# ScoreBoard-V2.net
KiCad netlist of a schematic drawn in EAGLE
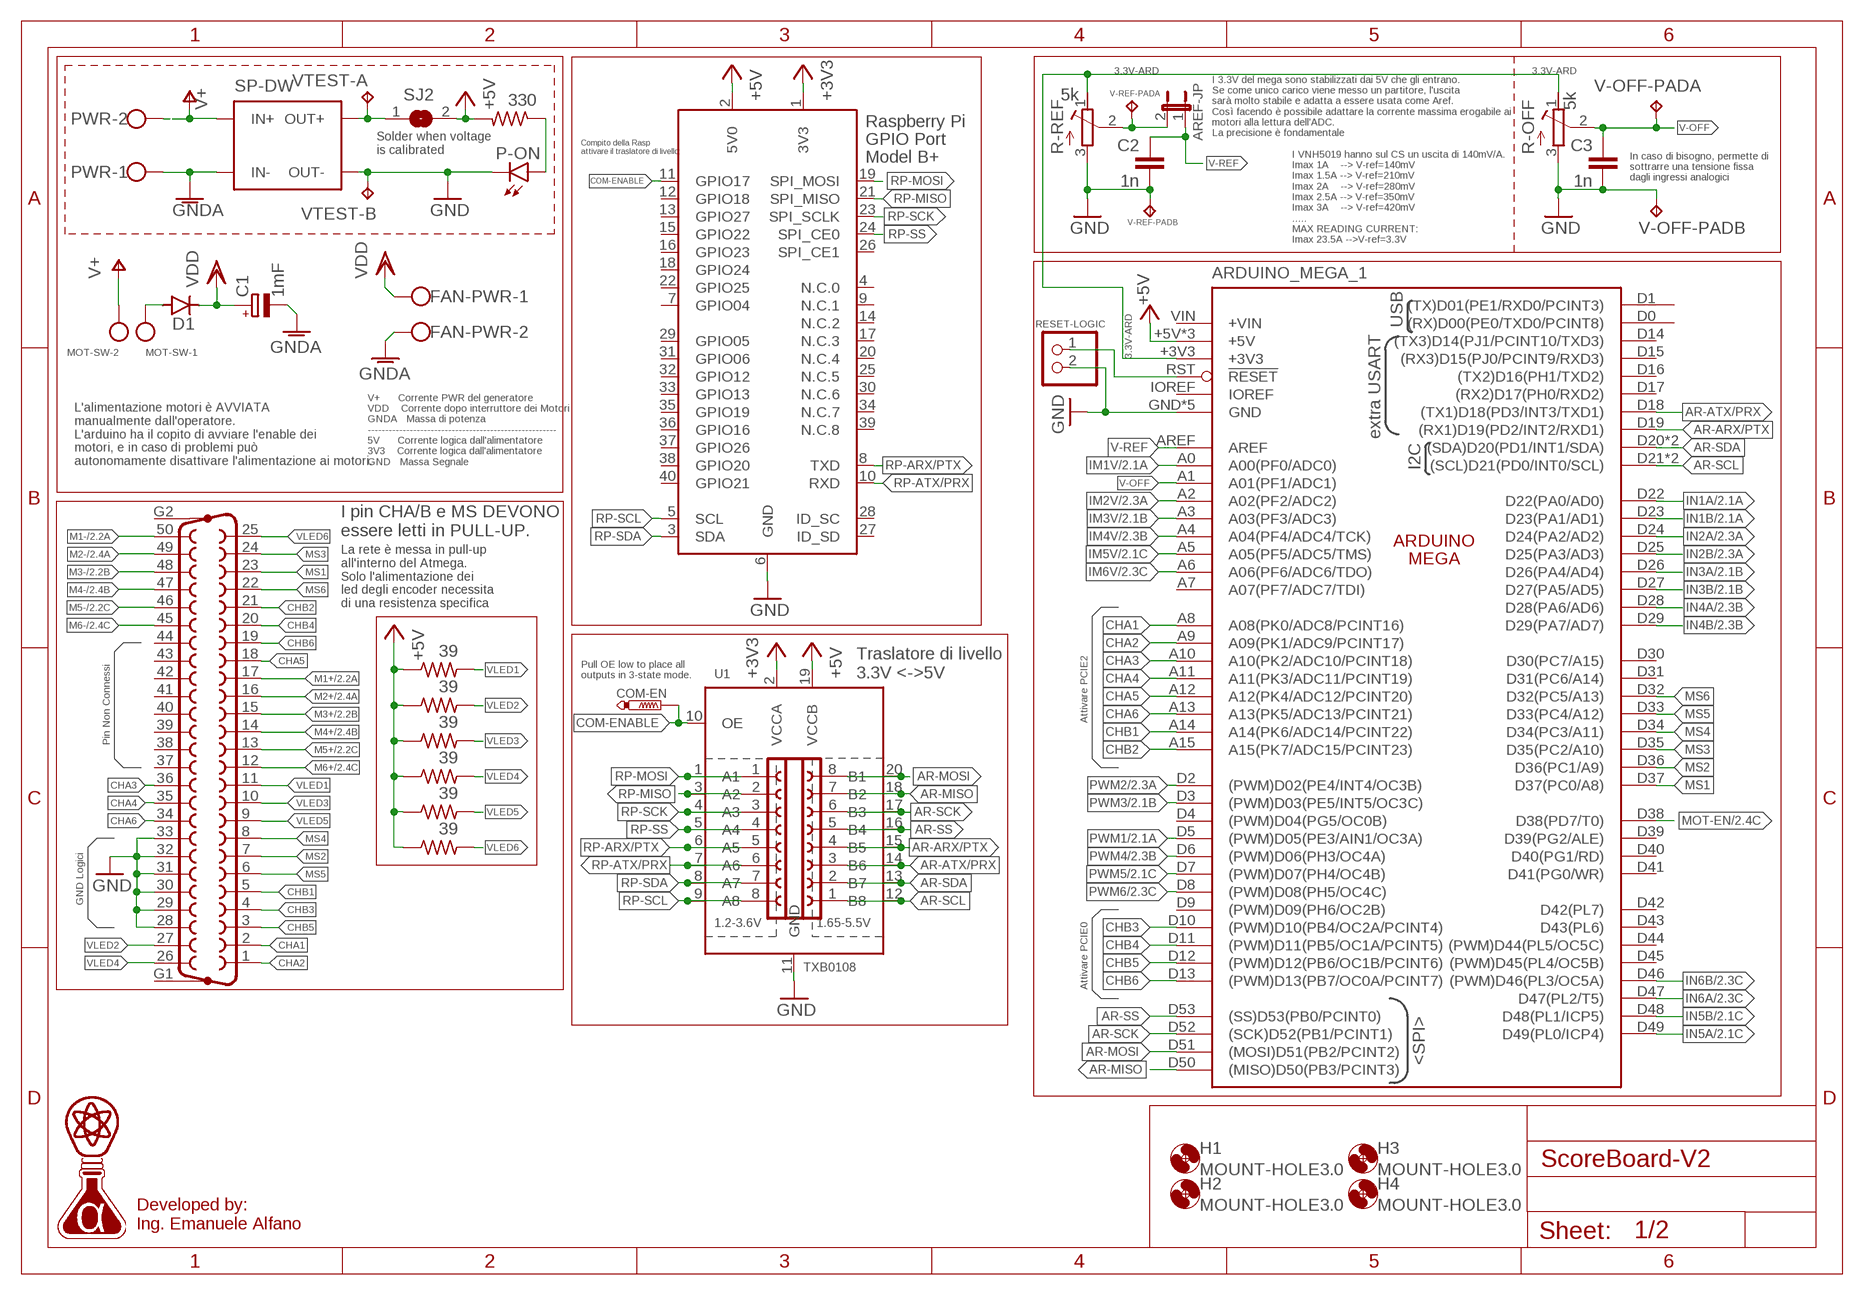
[diagram p0: schematic, sheet 1]
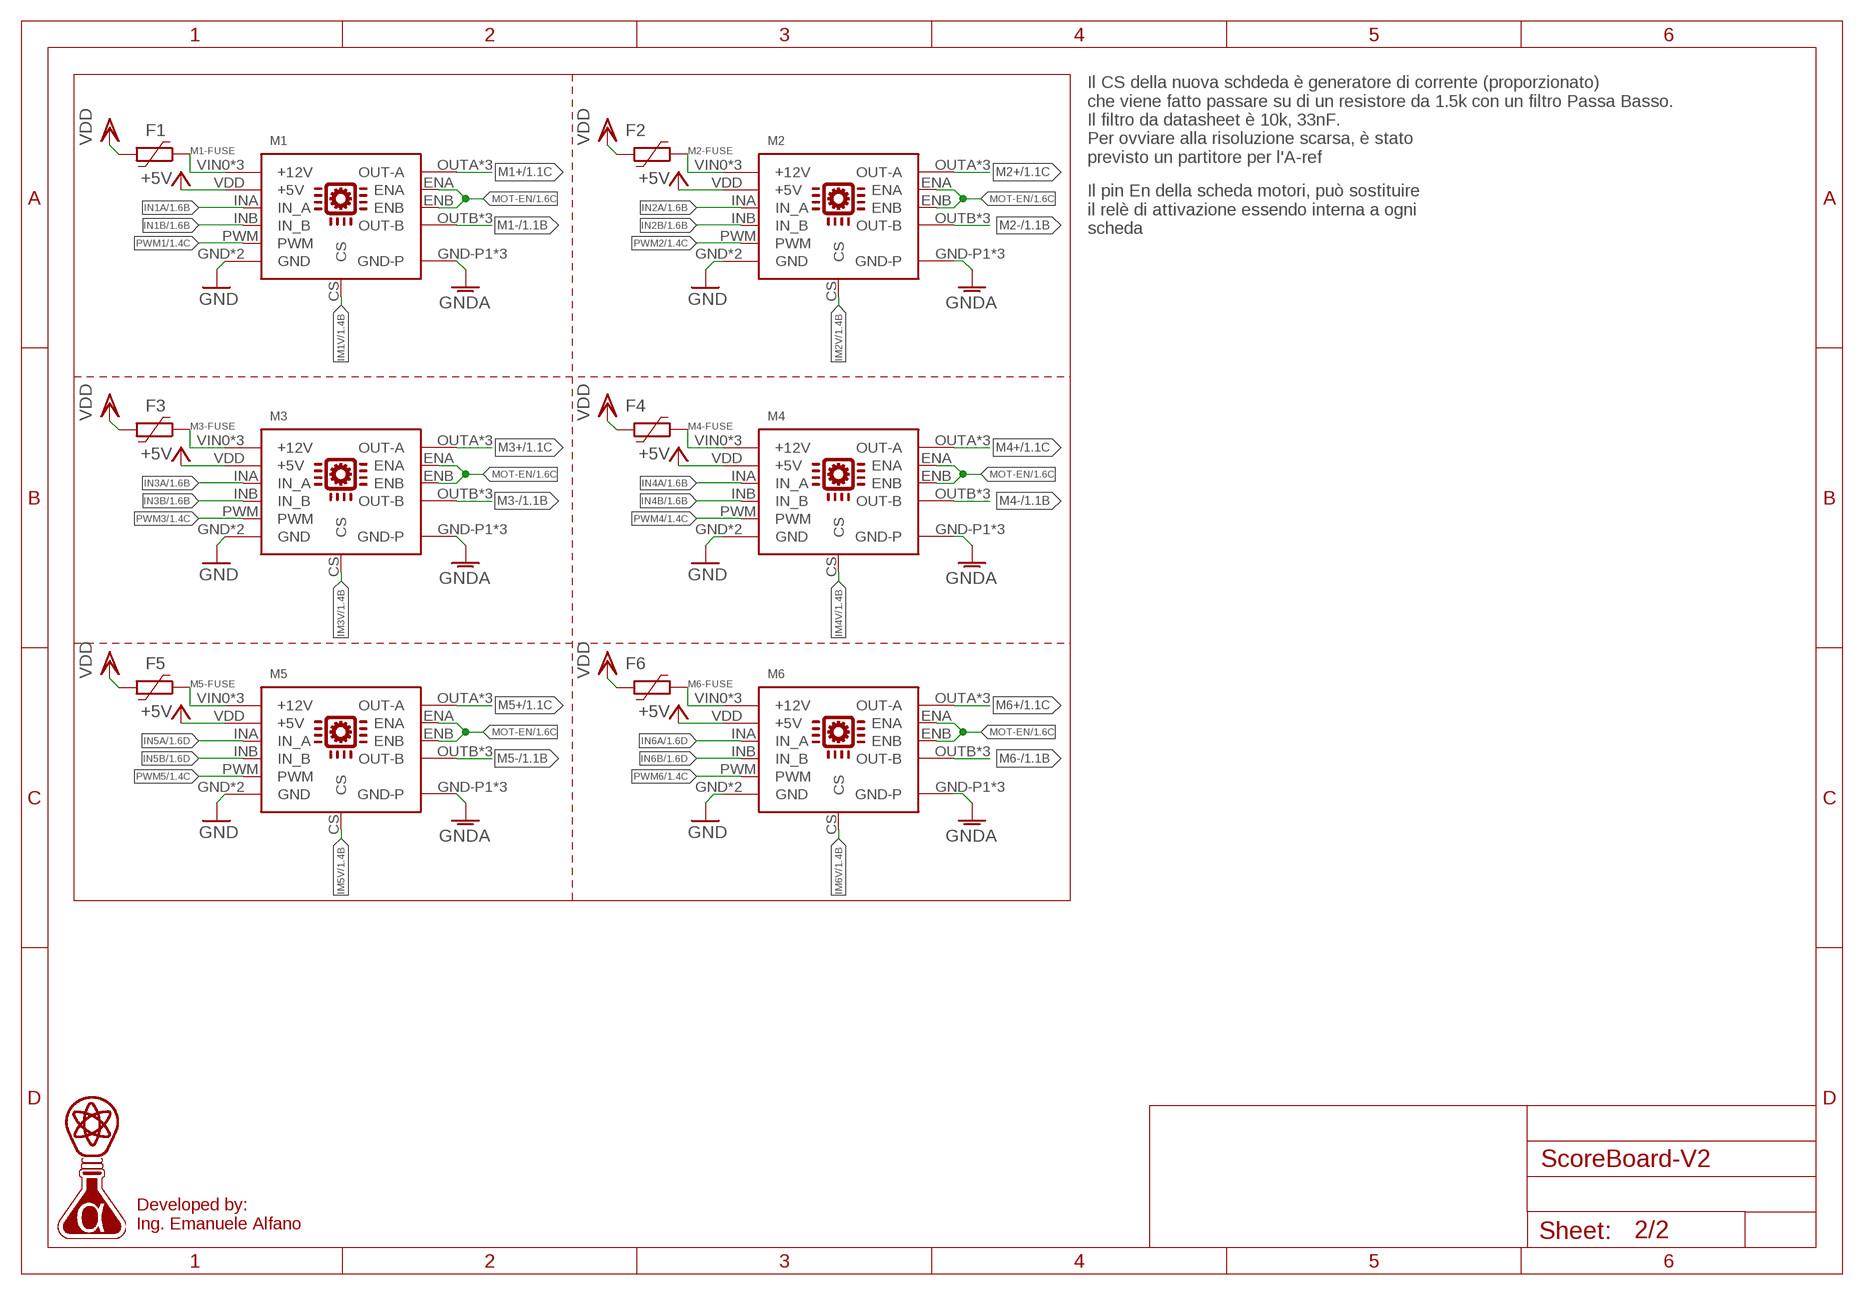
[diagram p1: schematic, sheet 2]

(export (version "E")
  (design (tool "Eeschema 10.0.6"))
  (components
    (comp (ref "F1")
      (value "2410-BOX")
      (footprint "eagle-import:BELFUSE0679-3000-12")
      (libsource (lib "eagle-import") (part "?2410-BOX"))
    )
    (comp (ref "F2")
      (value "2410-BOX")
      (footprint "eagle-import:BELFUSE0679-3000-12")
      (libsource (lib "eagle-import") (part "?2410-BOX"))
    )
    (comp (ref "F3")
      (value "2410-BOX")
      (footprint "eagle-import:BELFUSE0679-3000-12")
      (libsource (lib "eagle-import") (part "?2410-BOX"))
    )
    (comp (ref "F4")
      (value "2410-BOX")
      (footprint "eagle-import:BELFUSE0679-3000-12")
      (libsource (lib "eagle-import") (part "?2410-BOX"))
    )
    (comp (ref "F5")
      (value "2410-BOX")
      (footprint "eagle-import:BELFUSE0679-3000-12")
      (libsource (lib "eagle-import") (part "?2410-BOX"))
    )
    (comp (ref "F6")
      (value "2410-BOX")
      (footprint "eagle-import:BELFUSE0679-3000-12")
      (libsource (lib "eagle-import") (part "?2410-BOX"))
    )
    (comp (ref "M1")
      (value "VNH5019")
      (footprint "eagle-import:VNH5019")
      (libsource (lib "eagle-import") (part "VNH5019"))
    )
    (comp (ref "M2")
      (value "VNH5019")
      (footprint "eagle-import:VNH5019")
      (libsource (lib "eagle-import") (part "VNH5019"))
    )
    (comp (ref "M3")
      (value "VNH5019")
      (footprint "eagle-import:VNH5019")
      (libsource (lib "eagle-import") (part "VNH5019"))
    )
    (comp (ref "M4")
      (value "VNH5019")
      (footprint "eagle-import:VNH5019")
      (libsource (lib "eagle-import") (part "VNH5019"))
    )
    (comp (ref "M5")
      (value "VNH5019")
      (footprint "eagle-import:VNH5019")
      (libsource (lib "eagle-import") (part "VNH5019"))
    )
    (comp (ref "M6")
      (value "VNH5019")
      (footprint "eagle-import:VNH5019")
      (libsource (lib "eagle-import") (part "VNH5019"))
    )
    (comp (ref "ARDUINO_MEGA_1")
      (value "MEGA_ARDUINONO-HOLE")
      (footprint "eagle-import:MEGA-NO-HOLE")
      (libsource (lib "eagle-import") (part "MEGA_ARDUINONO-HOLE"))
    )
    (comp (ref "AREF-JP")
      (value "JP1E")
      (footprint "eagle-import:JP1")
      (libsource (lib "eagle-import") (part "JP1E"))
    )
    (comp (ref "C1")
      (value "1mF")
      (footprint "eagle-import:E5-13")
      (libsource (lib "eagle-import") (part "CPOL-EUE5-13"))
    )
    (comp (ref "C2")
      (value "1n")
      (footprint "eagle-import:C025-024X044")
      (libsource (lib "eagle-import") (part "C-EU025-024X044"))
    )
    (comp (ref "C3")
      (value "1n")
      (footprint "eagle-import:C025-024X044")
      (libsource (lib "eagle-import") (part "C-EU025-024X044"))
    )
    (comp (ref "COM-EN")
      (value "PTR1PAD1-13")
      (footprint "eagle-import:P1-13")
      (libsource (lib "eagle-import") (part "PTR1PAD1-13"))
    )
    (comp (ref "D-SUB50")
      (value "F50VP")
      (footprint "eagle-import:F50VP")
      (libsource (lib "eagle-import") (part "F50VP"))
    )
    (comp (ref "D1")
      (value "ES2D")
      (footprint "eagle-import:SMB")
      (libsource (lib "eagle-import") (part "ES2D"))
    )
    (comp (ref "FAN-PWR")
      (value "W237-102")
      (footprint "eagle-import:W237-102")
      (fields (field (name "MPN") "237-102"))
      (libsource (lib "eagle-import") (part "W237-102"))
    )
    (comp (ref "H1")
      (value "MOUNT-HOLE3.0")
      (footprint "eagle-import:3,0")
      (libsource (lib "eagle-import") (part "MOUNT-HOLE3.0"))
    )
    (comp (ref "H2")
      (value "MOUNT-HOLE3.0")
      (footprint "eagle-import:3,0")
      (libsource (lib "eagle-import") (part "MOUNT-HOLE3.0"))
    )
    (comp (ref "H3")
      (value "MOUNT-HOLE3.0")
      (footprint "eagle-import:3,0")
      (libsource (lib "eagle-import") (part "MOUNT-HOLE3.0"))
    )
    (comp (ref "H4")
      (value "MOUNT-HOLE3.0")
      (footprint "eagle-import:3,0")
      (libsource (lib "eagle-import") (part "MOUNT-HOLE3.0"))
    )
    (comp (ref "MOT-SW")
      (value "W237-102")
      (footprint "eagle-import:W237-102")
      (fields (field (name "MPN") "237-102"))
      (libsource (lib "eagle-import") (part "W237-102"))
    )
    (comp (ref "P-ON")
      (value "LED3MM")
      (footprint "eagle-import:LED3MM")
      (libsource (lib "eagle-import") (part "LED3MM"))
    )
    (comp (ref "PWR")
      (value "W237-102")
      (footprint "eagle-import:W237-102")
      (fields (field (name "MPN") "237-102"))
      (libsource (lib "eagle-import") (part "W237-102"))
    )
    (comp (ref "R-OFF")
      (value "5k")
      (footprint "eagle-import:RTRIMT93YA")
      (libsource (lib "eagle-import") (part "R-TRIMMT93YA"))
    )
    (comp (ref "R-REF")
      (value "5k")
      (footprint "eagle-import:RTRIMT93YA")
      (libsource (lib "eagle-import") (part "R-TRIMMT93YA"))
    )
    (comp (ref "R1")
      (value "39")
      (footprint "eagle-import:0204_5")
      (libsource (lib "eagle-import") (part "R-US_0204/5"))
    )
    (comp (ref "R2")
      (value "39")
      (footprint "eagle-import:0204_5")
      (libsource (lib "eagle-import") (part "R-US_0204/5"))
    )
    (comp (ref "R3")
      (value "39")
      (footprint "eagle-import:0204_5")
      (libsource (lib "eagle-import") (part "R-US_0204/5"))
    )
    (comp (ref "R4")
      (value "39")
      (footprint "eagle-import:0204_5")
      (libsource (lib "eagle-import") (part "R-US_0204/5"))
    )
    (comp (ref "R5")
      (value "39")
      (footprint "eagle-import:0204_5")
      (libsource (lib "eagle-import") (part "R-US_0204/5"))
    )
    (comp (ref "R6")
      (value "39")
      (footprint "eagle-import:0204_5")
      (libsource (lib "eagle-import") (part "R-US_0204/5"))
    )
    (comp (ref "RASPBERRY-PY")
      (value "RASPI_GPIO_B+_BOX")
      (footprint "eagle-import:RASPI_GPIO_B+_BOX")
      (libsource (lib "eagle-import") (part "RASPI_GPIO_B+_BOX"))
    )
    (comp (ref "RESET-LOGIC")
      (value "PINHD-1X2")
      (footprint "eagle-import:1X02")
      (libsource (lib "eagle-import") (part "PINHD-1X2"))
    )
    (comp (ref "RL")
      (value "330")
      (footprint "eagle-import:0204_7")
      (libsource (lib "eagle-import") (part "R-US_0204/7"))
    )
    (comp (ref "SJ2")
      (value "SJ")
      (footprint "eagle-import:SJ")
      (fields (field (name "SPICEPREFIX") "B"))
      (libsource (lib "eagle-import") (part "SJ"))
    )
    (comp (ref "SP-DW")
      (value "DC/DC-STEP-DOWNGLOB")
      (footprint "eagle-import:DC_DC-STEP-DOWN-UNIVERSAL")
      (libsource (lib "eagle-import") (part "DC/DC-STEP-DOWNGLOB"))
    )
    (comp (ref "SV1")
      (value "FE08-1")
      (footprint "eagle-import:FE08")
      (libsource (lib "eagle-import") (part "FE08-1"))
    )
    (comp (ref "SV2")
      (value "FE08-1")
      (footprint "eagle-import:FE08")
      (libsource (lib "eagle-import") (part "FE08-1"))
    )
    (comp (ref "U1")
      (value "TXB0108")
      (footprint "eagle-import:TSSOP20")
      (fields (field (name "MF") "Texas Instruments") (field (name "MP") "TXB0108PWR"))
      (libsource (lib "eagle-import") (part "TXB0108PWR"))
    )
    (comp (ref "V-OFF-PAD")
      (value "TP2P2-38-17")
      (footprint "eagle-import:P2-38-17")
      (fields (field (name "SPICEPREFIX") "X"))
      (libsource (lib "eagle-import") (part "TP2P2-38-17"))
    )
    (comp (ref "V-REF-PAD")
      (value "TP2P2-38-17")
      (footprint "eagle-import:P2-38-17")
      (fields (field (name "SPICEPREFIX") "X"))
      (libsource (lib "eagle-import") (part "TP2P2-38-17"))
    )
    (comp (ref "VTEST-")
      (value "TP2P2-38-17")
      (footprint "eagle-import:P2-38-17")
      (fields (field (name "SPICEPREFIX") "X"))
      (libsource (lib "eagle-import") (part "TP2P2-38-17"))
    )
  )
  (nets
    (net (code "1") (name "+3V3") (class "Default")
      (node (ref "RASPBERRY-PY") (pin "1") (pinfunction "3V3_1") (pintype "power_in"))
      (node (ref "U1") (pin "2") (pinfunction "VCCA_2") (pintype "bidirectional"))
    )
    (net (code "2") (name "+5V") (class "Default")
      (node (ref "ARDUINO_MEGA_1") (pin "+5V") (pinfunction "+5V_+5V") (pintype "bidirectional"))
      (node (ref "ARDUINO_MEGA_1") (pin "+5V1") (pinfunction "+5V_+5V1") (pintype "bidirectional"))
      (node (ref "ARDUINO_MEGA_1") (pin "+5V2") (pinfunction "+5V_+5V2") (pintype "bidirectional"))
      (node (ref "M1") (pin "VDD") (pinfunction "+5V_VDD") (pintype "bidirectional"))
      (node (ref "M2") (pin "VDD") (pinfunction "+5V_VDD") (pintype "bidirectional"))
      (node (ref "M3") (pin "VDD") (pinfunction "+5V_VDD") (pintype "bidirectional"))
      (node (ref "M4") (pin "VDD") (pinfunction "+5V_VDD") (pintype "bidirectional"))
      (node (ref "M5") (pin "VDD") (pinfunction "+5V_VDD") (pintype "bidirectional"))
      (node (ref "M6") (pin "VDD") (pinfunction "+5V_VDD") (pintype "bidirectional"))
      (node (ref "R1") (pin "1") (pinfunction "1_1") (pintype "passive"))
      (node (ref "R2") (pin "1") (pinfunction "1_1") (pintype "passive"))
      (node (ref "R3") (pin "1") (pinfunction "1_1") (pintype "passive"))
      (node (ref "R4") (pin "1") (pinfunction "1_1") (pintype "passive"))
      (node (ref "R5") (pin "1") (pinfunction "1_1") (pintype "passive"))
      (node (ref "R6") (pin "1") (pinfunction "1_1") (pintype "passive"))
      (node (ref "RASPBERRY-PY") (pin "2") (pinfunction "5V0_2") (pintype "power_in"))
      (node (ref "RL") (pin "2") (pinfunction "2_2") (pintype "passive"))
      (node (ref "SJ2") (pin "2") (pinfunction "2_2") (pintype "passive"))
      (node (ref "U1") (pin "19") (pinfunction "VCCB_19") (pintype "bidirectional"))
    )
    (net (code "3") (name "3.3V-ARD") (class "Default")
      (node (ref "ARDUINO_MEGA_1") (pin "+3V3") (pinfunction "+3V3_+3V3") (pintype "bidirectional"))
      (node (ref "R-OFF") (pin "1") (pinfunction "E_1") (pintype "passive"))
      (node (ref "R-REF") (pin "1") (pinfunction "E_1") (pintype "passive"))
    )
    (net (code "4") (name "AR-ARX{slash}PTX") (class "Default")
      (node (ref "ARDUINO_MEGA_1") (pin "D19") (pinfunction "(RX1)D19(PD2/INT2/RXD1)_D19") (pintype "bidirectional"))
      (node (ref "SV2") (pin "4") (pinfunction "4_4") (pintype "passive"))
      (node (ref "U1") (pin "15") (pinfunction "B5_15") (pintype "bidirectional"))
    )
    (net (code "5") (name "AR-ATX{slash}PRX") (class "Default")
      (node (ref "ARDUINO_MEGA_1") (pin "D18") (pinfunction "(TX1)D18(PD3/INT3/TXD1)_D18") (pintype "bidirectional"))
      (node (ref "SV2") (pin "3") (pinfunction "3_3") (pintype "passive"))
      (node (ref "U1") (pin "14") (pinfunction "B6_14") (pintype "bidirectional"))
    )
    (net (code "6") (name "AR-MISO") (class "Default")
      (node (ref "ARDUINO_MEGA_1") (pin "D50") (pinfunction "(MISO)D50(PB3/PCINT3)_D50") (pintype "bidirectional"))
      (node (ref "SV2") (pin "7") (pinfunction "7_7") (pintype "passive"))
      (node (ref "U1") (pin "18") (pinfunction "B2_18") (pintype "bidirectional"))
    )
    (net (code "7") (name "AR-MOSI") (class "Default")
      (node (ref "ARDUINO_MEGA_1") (pin "D51") (pinfunction "(MOSI)D51(PB2/PCINT2)_D51") (pintype "bidirectional"))
      (node (ref "SV2") (pin "8") (pinfunction "8_8") (pintype "passive"))
      (node (ref "U1") (pin "20") (pinfunction "B1_20") (pintype "bidirectional"))
    )
    (net (code "8") (name "AR-SCK") (class "Default")
      (node (ref "ARDUINO_MEGA_1") (pin "D52") (pinfunction "(SCK)D52(PB1/PCINT1)_D52") (pintype "bidirectional"))
      (node (ref "SV2") (pin "6") (pinfunction "6_6") (pintype "passive"))
      (node (ref "U1") (pin "17") (pinfunction "B3_17") (pintype "bidirectional"))
    )
    (net (code "9") (name "AR-SCL") (class "Default")
      (node (ref "ARDUINO_MEGA_1") (pin "D21") (pinfunction "(SCL)D21(PD0/INT0/SCL)_D21") (pintype "bidirectional"))
      (node (ref "ARDUINO_MEGA_1") (pin "SCL1") (pinfunction "(SCL)D21(PD0/INT0/SCL)_SCL1") (pintype "bidirectional"))
      (node (ref "SV2") (pin "1") (pinfunction "1_1") (pintype "passive"))
      (node (ref "U1") (pin "12") (pinfunction "B8_12") (pintype "bidirectional"))
    )
    (net (code "10") (name "AR-SDA") (class "Default")
      (node (ref "ARDUINO_MEGA_1") (pin "D20") (pinfunction "(SDA)D20(PD1/INT1/SDA)_D20") (pintype "bidirectional"))
      (node (ref "ARDUINO_MEGA_1") (pin "SDA1") (pinfunction "(SDA)D20(PD1/INT1/SDA)_SDA1") (pintype "bidirectional"))
      (node (ref "SV2") (pin "2") (pinfunction "2_2") (pintype "passive"))
      (node (ref "U1") (pin "13") (pinfunction "B7_13") (pintype "bidirectional"))
    )
    (net (code "11") (name "AR-SS") (class "Default")
      (node (ref "ARDUINO_MEGA_1") (pin "D53") (pinfunction "(SS)D53(PB0/PCINT0)_D53") (pintype "bidirectional"))
      (node (ref "SV2") (pin "5") (pinfunction "5_5") (pintype "passive"))
      (node (ref "U1") (pin "16") (pinfunction "B4_16") (pintype "bidirectional"))
    )
    (net (code "12") (name "CHA1") (class "Default")
      (node (ref "ARDUINO_MEGA_1") (pin "A8") (pinfunction "A08(PK0/ADC8/PCINT16)_A8") (pintype "bidirectional"))
      (node (ref "D-SUB50") (pin "2") (pinfunction "2_2") (pintype "passive"))
    )
    (net (code "13") (name "CHA2") (class "Default")
      (node (ref "ARDUINO_MEGA_1") (pin "A9") (pinfunction "A09(PK1/ADC9/PCINT17)_A9") (pintype "bidirectional"))
      (node (ref "D-SUB50") (pin "1") (pinfunction "1_1") (pintype "passive"))
    )
    (net (code "14") (name "CHA3") (class "Default")
      (node (ref "ARDUINO_MEGA_1") (pin "A10") (pinfunction "A10(PK2/ADC10/PCINT18)_A10") (pintype "bidirectional"))
      (node (ref "D-SUB50") (pin "36") (pinfunction "36_36") (pintype "passive"))
    )
    (net (code "15") (name "CHA4") (class "Default")
      (node (ref "ARDUINO_MEGA_1") (pin "A11") (pinfunction "A11(PK3/ADC11/PCINT19)_A11") (pintype "bidirectional"))
      (node (ref "D-SUB50") (pin "35") (pinfunction "35_35") (pintype "passive"))
    )
    (net (code "16") (name "CHA5") (class "Default")
      (node (ref "ARDUINO_MEGA_1") (pin "A12") (pinfunction "A12(PK4/ADC12/PCINT20)_A12") (pintype "bidirectional"))
      (node (ref "D-SUB50") (pin "18") (pinfunction "18_18") (pintype "passive"))
    )
    (net (code "17") (name "CHA6") (class "Default")
      (node (ref "ARDUINO_MEGA_1") (pin "A13") (pinfunction "A13(PK5/ADC13/PCINT21)_A13") (pintype "bidirectional"))
      (node (ref "D-SUB50") (pin "34") (pinfunction "34_34") (pintype "passive"))
    )
    (net (code "18") (name "CHB1") (class "Default")
      (node (ref "ARDUINO_MEGA_1") (pin "A14") (pinfunction "A14(PK6/ADC14/PCINT22)_A14") (pintype "bidirectional"))
      (node (ref "D-SUB50") (pin "5") (pinfunction "5_5") (pintype "passive"))
    )
    (net (code "19") (name "CHB2") (class "Default")
      (node (ref "ARDUINO_MEGA_1") (pin "A15") (pinfunction "A15(PK7/ADC15/PCINT23)_A15") (pintype "bidirectional"))
      (node (ref "D-SUB50") (pin "21") (pinfunction "21_21") (pintype "passive"))
    )
    (net (code "20") (name "CHB3") (class "Default")
      (node (ref "ARDUINO_MEGA_1") (pin "D10") (pinfunction "(PWM)D10(PB4/OC2A/PCINT4)_D10") (pintype "bidirectional"))
      (node (ref "D-SUB50") (pin "4") (pinfunction "4_4") (pintype "passive"))
    )
    (net (code "21") (name "CHB4") (class "Default")
      (node (ref "ARDUINO_MEGA_1") (pin "D11") (pinfunction "(PWM)D11(PB5/OC1A/PCINT5)_D11") (pintype "bidirectional"))
      (node (ref "D-SUB50") (pin "20") (pinfunction "20_20") (pintype "passive"))
    )
    (net (code "22") (name "CHB5") (class "Default")
      (node (ref "ARDUINO_MEGA_1") (pin "D12") (pinfunction "(PWM)D12(PB6/OC1B/PCINT6)_D12") (pintype "bidirectional"))
      (node (ref "D-SUB50") (pin "3") (pinfunction "3_3") (pintype "passive"))
    )
    (net (code "23") (name "CHB6") (class "Default")
      (node (ref "ARDUINO_MEGA_1") (pin "D13") (pinfunction "(PWM)D13(PB7/OC0A/PCINT7)_D13") (pintype "bidirectional"))
      (node (ref "D-SUB50") (pin "19") (pinfunction "19_19") (pintype "passive"))
    )
    (net (code "24") (name "COM-ENABLE") (class "Default")
      (node (ref "COM-EN") (pin "TP") (pinfunction "TP_TP") (pintype "input"))
      (node (ref "RASPBERRY-PY") (pin "11") (pinfunction "GPIO17_11") (pintype "bidirectional"))
      (node (ref "U1") (pin "10") (pinfunction "OE_10") (pintype "bidirectional"))
    )
    (net (code "25") (name "GND") (class "Default")
      (node (ref "ARDUINO_MEGA_1") (pin "GND") (pinfunction "GND_GND") (pintype "bidirectional"))
      (node (ref "ARDUINO_MEGA_1") (pin "GND1") (pinfunction "GND_GND1") (pintype "bidirectional"))
      (node (ref "ARDUINO_MEGA_1") (pin "GND2") (pinfunction "GND_GND2") (pintype "bidirectional"))
      (node (ref "ARDUINO_MEGA_1") (pin "GND3") (pinfunction "GND_GND3") (pintype "bidirectional"))
      (node (ref "ARDUINO_MEGA_1") (pin "GND4") (pinfunction "GND_GND4") (pintype "bidirectional"))
      (node (ref "C2") (pin "2") (pinfunction "2_2") (pintype "passive"))
      (node (ref "C3") (pin "2") (pinfunction "2_2") (pintype "passive"))
      (node (ref "D-SUB50") (pin "28") (pinfunction "28_28") (pintype "passive"))
      (node (ref "D-SUB50") (pin "29") (pinfunction "29_29") (pintype "passive"))
      (node (ref "D-SUB50") (pin "30") (pinfunction "30_30") (pintype "passive"))
      (node (ref "D-SUB50") (pin "31") (pinfunction "31_31") (pintype "passive"))
      (node (ref "D-SUB50") (pin "32") (pinfunction "32_32") (pintype "passive"))
      (node (ref "D-SUB50") (pin "33") (pinfunction "33_33") (pintype "passive"))
      (node (ref "M1") (pin "GND") (pinfunction "GND_GND") (pintype "bidirectional"))
      (node (ref "M1") (pin "GND1") (pinfunction "GND_GND1") (pintype "bidirectional"))
      (node (ref "M2") (pin "GND") (pinfunction "GND_GND") (pintype "bidirectional"))
      (node (ref "M2") (pin "GND1") (pinfunction "GND_GND1") (pintype "bidirectional"))
      (node (ref "M3") (pin "GND") (pinfunction "GND_GND") (pintype "bidirectional"))
      (node (ref "M3") (pin "GND1") (pinfunction "GND_GND1") (pintype "bidirectional"))
      (node (ref "M4") (pin "GND") (pinfunction "GND_GND") (pintype "bidirectional"))
      (node (ref "M4") (pin "GND1") (pinfunction "GND_GND1") (pintype "bidirectional"))
      (node (ref "M5") (pin "GND") (pinfunction "GND_GND") (pintype "bidirectional"))
      (node (ref "M5") (pin "GND1") (pinfunction "GND_GND1") (pintype "bidirectional"))
      (node (ref "M6") (pin "GND") (pinfunction "GND_GND") (pintype "bidirectional"))
      (node (ref "M6") (pin "GND1") (pinfunction "GND_GND1") (pintype "bidirectional"))
      (node (ref "P-ON") (pin "K") (pinfunction "C_K") (pintype "passive"))
      (node (ref "R-OFF") (pin "3") (pinfunction "A_3") (pintype "passive"))
      (node (ref "R-REF") (pin "3") (pinfunction "A_3") (pintype "passive"))
      (node (ref "RASPBERRY-PY") (pin "6") (pinfunction "GND_6") (pintype "power_in"))
      (node (ref "RESET-LOGIC") (pin "2") (pinfunction "2_2") (pintype "passive"))
      (node (ref "SP-DW") (pin "OUT-") (pinfunction "OUT-_OUT-") (pintype "bidirectional"))
      (node (ref "SP-DW") (pin "OUT-1") (pinfunction "OUT-_OUT-1") (pintype "bidirectional"))
      (node (ref "SP-DW") (pin "OUT-2") (pinfunction "OUT-_OUT-2") (pintype "bidirectional"))
      (node (ref "U1") (pin "11") (pinfunction "GND_11") (pintype "bidirectional"))
      (node (ref "V-OFF-PAD") (pin "TP-2") (pinfunction "TP_TP-2") (pintype "input"))
      (node (ref "V-REF-PAD") (pin "TP-2") (pinfunction "TP_TP-2") (pintype "input"))
      (node (ref "VTEST-") (pin "TP-2") (pinfunction "TP_TP-2") (pintype "input"))
    )
    (net (code "26") (name "GNDA") (class "Default")
      (node (ref "C1") (pin "-") (pinfunction "-_-") (pintype "passive"))
      (node (ref "FAN-PWR") (pin "2") (pinfunction "KL_2") (pintype "passive"))
      (node (ref "M1") (pin "GND-P1") (pinfunction "GND-P_GND-P1") (pintype "bidirectional"))
      (node (ref "M1") (pin "GND-P2") (pinfunction "GND-P_GND-P2") (pintype "bidirectional"))
      (node (ref "M1") (pin "GND-P3") (pinfunction "GND-P_GND-P3") (pintype "bidirectional"))
      (node (ref "M2") (pin "GND-P1") (pinfunction "GND-P_GND-P1") (pintype "bidirectional"))
      (node (ref "M2") (pin "GND-P2") (pinfunction "GND-P_GND-P2") (pintype "bidirectional"))
      (node (ref "M2") (pin "GND-P3") (pinfunction "GND-P_GND-P3") (pintype "bidirectional"))
      (node (ref "M3") (pin "GND-P1") (pinfunction "GND-P_GND-P1") (pintype "bidirectional"))
      (node (ref "M3") (pin "GND-P2") (pinfunction "GND-P_GND-P2") (pintype "bidirectional"))
      (node (ref "M3") (pin "GND-P3") (pinfunction "GND-P_GND-P3") (pintype "bidirectional"))
      (node (ref "M4") (pin "GND-P1") (pinfunction "GND-P_GND-P1") (pintype "bidirectional"))
      (node (ref "M4") (pin "GND-P2") (pinfunction "GND-P_GND-P2") (pintype "bidirectional"))
      (node (ref "M4") (pin "GND-P3") (pinfunction "GND-P_GND-P3") (pintype "bidirectional"))
      (node (ref "M5") (pin "GND-P1") (pinfunction "GND-P_GND-P1") (pintype "bidirectional"))
      (node (ref "M5") (pin "GND-P2") (pinfunction "GND-P_GND-P2") (pintype "bidirectional"))
      (node (ref "M5") (pin "GND-P3") (pinfunction "GND-P_GND-P3") (pintype "bidirectional"))
      (node (ref "M6") (pin "GND-P1") (pinfunction "GND-P_GND-P1") (pintype "bidirectional"))
      (node (ref "M6") (pin "GND-P2") (pinfunction "GND-P_GND-P2") (pintype "bidirectional"))
      (node (ref "M6") (pin "GND-P3") (pinfunction "GND-P_GND-P3") (pintype "bidirectional"))
      (node (ref "PWR") (pin "1") (pinfunction "KL_1") (pintype "passive"))
      (node (ref "SP-DW") (pin "IN-") (pinfunction "IN-_IN-") (pintype "bidirectional"))
      (node (ref "SP-DW") (pin "IN-1") (pinfunction "IN-_IN-1") (pintype "bidirectional"))
      (node (ref "SP-DW") (pin "IN-2") (pinfunction "IN-_IN-2") (pintype "bidirectional"))
    )
    (net (code "27") (name "IM1V") (class "Default")
      (node (ref "ARDUINO_MEGA_1") (pin "A0") (pinfunction "A00(PF0/ADC0)_A0") (pintype "bidirectional"))
      (node (ref "M1") (pin "CS") (pinfunction "CS_CS") (pintype "bidirectional"))
    )
    (net (code "28") (name "IM2V") (class "Default")
      (node (ref "ARDUINO_MEGA_1") (pin "A2") (pinfunction "A02(PF2/ADC2)_A2") (pintype "bidirectional"))
      (node (ref "M2") (pin "CS") (pinfunction "CS_CS") (pintype "bidirectional"))
    )
    (net (code "29") (name "IM3V") (class "Default")
      (node (ref "ARDUINO_MEGA_1") (pin "A3") (pinfunction "A03(PF3/ADC3)_A3") (pintype "bidirectional"))
      (node (ref "M3") (pin "CS") (pinfunction "CS_CS") (pintype "bidirectional"))
    )
    (net (code "30") (name "IM4V") (class "Default")
      (node (ref "ARDUINO_MEGA_1") (pin "A4") (pinfunction "A04(PF4/ADC4/TCK)_A4") (pintype "bidirectional"))
      (node (ref "M4") (pin "CS") (pinfunction "CS_CS") (pintype "bidirectional"))
    )
    (net (code "31") (name "IM5V") (class "Default")
      (node (ref "ARDUINO_MEGA_1") (pin "A5") (pinfunction "A05(PF5/ADC5/TMS)_A5") (pintype "bidirectional"))
      (node (ref "M5") (pin "CS") (pinfunction "CS_CS") (pintype "bidirectional"))
    )
    (net (code "32") (name "IM6V") (class "Default")
      (node (ref "ARDUINO_MEGA_1") (pin "A6") (pinfunction "A06(PF6/ADC6/TDO)_A6") (pintype "bidirectional"))
      (node (ref "M6") (pin "CS") (pinfunction "CS_CS") (pintype "bidirectional"))
    )
    (net (code "33") (name "IN1A") (class "Default")
      (node (ref "ARDUINO_MEGA_1") (pin "D22") (pinfunction "D22(PA0/AD0)_D22") (pintype "bidirectional"))
      (node (ref "M1") (pin "INA") (pinfunction "IN_A_INA") (pintype "bidirectional"))
    )
    (net (code "34") (name "IN1B") (class "Default")
      (node (ref "ARDUINO_MEGA_1") (pin "D23") (pinfunction "D23(PA1/AD1)_D23") (pintype "bidirectional"))
      (node (ref "M1") (pin "INB") (pinfunction "IN_B_INB") (pintype "bidirectional"))
    )
    (net (code "35") (name "IN2A") (class "Default")
      (node (ref "ARDUINO_MEGA_1") (pin "D24") (pinfunction "D24(PA2/AD2)_D24") (pintype "bidirectional"))
      (node (ref "M2") (pin "INA") (pinfunction "IN_A_INA") (pintype "bidirectional"))
    )
    (net (code "36") (name "IN2B") (class "Default")
      (node (ref "ARDUINO_MEGA_1") (pin "D25") (pinfunction "D25(PA3/AD3)_D25") (pintype "bidirectional"))
      (node (ref "M2") (pin "INB") (pinfunction "IN_B_INB") (pintype "bidirectional"))
    )
    (net (code "37") (name "IN3A") (class "Default")
      (node (ref "ARDUINO_MEGA_1") (pin "D26") (pinfunction "D26(PA4/AD4)_D26") (pintype "bidirectional"))
      (node (ref "M3") (pin "INA") (pinfunction "IN_A_INA") (pintype "bidirectional"))
    )
    (net (code "38") (name "IN3B") (class "Default")
      (node (ref "ARDUINO_MEGA_1") (pin "D27") (pinfunction "D27(PA5/AD5)_D27") (pintype "bidirectional"))
      (node (ref "M3") (pin "INB") (pinfunction "IN_B_INB") (pintype "bidirectional"))
    )
    (net (code "39") (name "IN4A") (class "Default")
      (node (ref "ARDUINO_MEGA_1") (pin "D28") (pinfunction "D28(PA6/AD6)_D28") (pintype "bidirectional"))
      (node (ref "M4") (pin "INA") (pinfunction "IN_A_INA") (pintype "bidirectional"))
    )
    (net (code "40") (name "IN4B") (class "Default")
      (node (ref "ARDUINO_MEGA_1") (pin "D29") (pinfunction "D29(PA7/AD7)_D29") (pintype "bidirectional"))
      (node (ref "M4") (pin "INB") (pinfunction "IN_B_INB") (pintype "bidirectional"))
    )
    (net (code "41") (name "IN5A") (class "Default")
      (node (ref "ARDUINO_MEGA_1") (pin "D49") (pinfunction "D49(PL0/ICP4)_D49") (pintype "bidirectional"))
      (node (ref "M5") (pin "INA") (pinfunction "IN_A_INA") (pintype "bidirectional"))
    )
    (net (code "42") (name "IN5B") (class "Default")
      (node (ref "ARDUINO_MEGA_1") (pin "D48") (pinfunction "D48(PL1/ICP5)_D48") (pintype "bidirectional"))
      (node (ref "M5") (pin "INB") (pinfunction "IN_B_INB") (pintype "bidirectional"))
    )
    (net (code "43") (name "IN6A") (class "Default")
      (node (ref "ARDUINO_MEGA_1") (pin "D47") (pinfunction "D47(PL2/T5)_D47") (pintype "bidirectional"))
      (node (ref "M6") (pin "INA") (pinfunction "IN_A_INA") (pintype "bidirectional"))
    )
    (net (code "44") (name "IN6B") (class "Default")
      (node (ref "ARDUINO_MEGA_1") (pin "D46") (pinfunction "(PWM)D46(PL3/OC5A)_D46") (pintype "bidirectional"))
      (node (ref "M6") (pin "INB") (pinfunction "IN_B_INB") (pintype "bidirectional"))
    )
    (net (code "45") (name "M1+") (class "Default")
      (node (ref "D-SUB50") (pin "17") (pinfunction "17_17") (pintype "passive"))
      (node (ref "M1") (pin "OUTA") (pinfunction "OUT-A_OUTA") (pintype "bidirectional"))
      (node (ref "M1") (pin "OUTA2") (pinfunction "OUT-A_OUTA2") (pintype "bidirectional"))
      (node (ref "M1") (pin "OUTA3") (pinfunction "OUT-A_OUTA3") (pintype "bidirectional"))
    )
    (net (code "46") (name "M1-") (class "Default")
      (node (ref "D-SUB50") (pin "50") (pinfunction "50_50") (pintype "passive"))
      (node (ref "M1") (pin "OUTB") (pinfunction "OUT-B_OUTB") (pintype "bidirectional"))
      (node (ref "M1") (pin "OUTB1") (pinfunction "OUT-B_OUTB1") (pintype "bidirectional"))
      (node (ref "M1") (pin "OUTB3") (pinfunction "OUT-B_OUTB3") (pintype "bidirectional"))
    )
    (net (code "47") (name "M1-FUSE") (class "Default")
      (node (ref "F1") (pin "1") (pinfunction "1_1") (pintype "passive"))
      (node (ref "M1") (pin "VIN0") (pinfunction "+12V_VIN0") (pintype "bidirectional"))
      (node (ref "M1") (pin "VIN1") (pinfunction "+12V_VIN1") (pintype "bidirectional"))
      (node (ref "M1") (pin "VIN2") (pinfunction "+12V_VIN2") (pintype "bidirectional"))
    )
    (net (code "48") (name "M2+") (class "Default")
      (node (ref "D-SUB50") (pin "16") (pinfunction "16_16") (pintype "passive"))
      (node (ref "M2") (pin "OUTA") (pinfunction "OUT-A_OUTA") (pintype "bidirectional"))
      (node (ref "M2") (pin "OUTA2") (pinfunction "OUT-A_OUTA2") (pintype "bidirectional"))
      (node (ref "M2") (pin "OUTA3") (pinfunction "OUT-A_OUTA3") (pintype "bidirectional"))
    )
    (net (code "49") (name "M2-") (class "Default")
      (node (ref "D-SUB50") (pin "49") (pinfunction "49_49") (pintype "passive"))
      (node (ref "M2") (pin "OUTB") (pinfunction "OUT-B_OUTB") (pintype "bidirectional"))
      (node (ref "M2") (pin "OUTB1") (pinfunction "OUT-B_OUTB1") (pintype "bidirectional"))
      (node (ref "M2") (pin "OUTB3") (pinfunction "OUT-B_OUTB3") (pintype "bidirectional"))
    )
    (net (code "50") (name "M2-FUSE") (class "Default")
      (node (ref "F2") (pin "1") (pinfunction "1_1") (pintype "passive"))
      (node (ref "M2") (pin "VIN0") (pinfunction "+12V_VIN0") (pintype "bidirectional"))
      (node (ref "M2") (pin "VIN1") (pinfunction "+12V_VIN1") (pintype "bidirectional"))
      (node (ref "M2") (pin "VIN2") (pinfunction "+12V_VIN2") (pintype "bidirectional"))
    )
    (net (code "51") (name "M3+") (class "Default")
      (node (ref "D-SUB50") (pin "15") (pinfunction "15_15") (pintype "passive"))
      (node (ref "M3") (pin "OUTA") (pinfunction "OUT-A_OUTA") (pintype "bidirectional"))
      (node (ref "M3") (pin "OUTA2") (pinfunction "OUT-A_OUTA2") (pintype "bidirectional"))
      (node (ref "M3") (pin "OUTA3") (pinfunction "OUT-A_OUTA3") (pintype "bidirectional"))
    )
    (net (code "52") (name "M3-") (class "Default")
      (node (ref "D-SUB50") (pin "48") (pinfunction "48_48") (pintype "passive"))
      (node (ref "M3") (pin "OUTB") (pinfunction "OUT-B_OUTB") (pintype "bidirectional"))
      (node (ref "M3") (pin "OUTB1") (pinfunction "OUT-B_OUTB1") (pintype "bidirectional"))
      (node (ref "M3") (pin "OUTB3") (pinfunction "OUT-B_OUTB3") (pintype "bidirectional"))
    )
    (net (code "53") (name "M3-FUSE") (class "Default")
      (node (ref "F3") (pin "1") (pinfunction "1_1") (pintype "passive"))
      (node (ref "M3") (pin "VIN0") (pinfunction "+12V_VIN0") (pintype "bidirectional"))
      (node (ref "M3") (pin "VIN1") (pinfunction "+12V_VIN1") (pintype "bidirectional"))
      (node (ref "M3") (pin "VIN2") (pinfunction "+12V_VIN2") (pintype "bidirectional"))
    )
    (net (code "54") (name "M4+") (class "Default")
      (node (ref "D-SUB50") (pin "14") (pinfunction "14_14") (pintype "passive"))
      (node (ref "M4") (pin "OUTA") (pinfunction "OUT-A_OUTA") (pintype "bidirectional"))
      (node (ref "M4") (pin "OUTA2") (pinfunction "OUT-A_OUTA2") (pintype "bidirectional"))
      (node (ref "M4") (pin "OUTA3") (pinfunction "OUT-A_OUTA3") (pintype "bidirectional"))
    )
    (net (code "55") (name "M4-") (class "Default")
      (node (ref "D-SUB50") (pin "47") (pinfunction "47_47") (pintype "passive"))
      (node (ref "M4") (pin "OUTB") (pinfunction "OUT-B_OUTB") (pintype "bidirectional"))
      (node (ref "M4") (pin "OUTB1") (pinfunction "OUT-B_OUTB1") (pintype "bidirectional"))
      (node (ref "M4") (pin "OUTB3") (pinfunction "OUT-B_OUTB3") (pintype "bidirectional"))
    )
    (net (code "56") (name "M4-FUSE") (class "Default")
      (node (ref "F4") (pin "1") (pinfunction "1_1") (pintype "passive"))
      (node (ref "M4") (pin "VIN0") (pinfunction "+12V_VIN0") (pintype "bidirectional"))
      (node (ref "M4") (pin "VIN1") (pinfunction "+12V_VIN1") (pintype "bidirectional"))
      (node (ref "M4") (pin "VIN2") (pinfunction "+12V_VIN2") (pintype "bidirectional"))
    )
    (net (code "57") (name "M5+") (class "Default")
      (node (ref "D-SUB50") (pin "13") (pinfunction "13_13") (pintype "passive"))
      (node (ref "M5") (pin "OUTA") (pinfunction "OUT-A_OUTA") (pintype "bidirectional"))
      (node (ref "M5") (pin "OUTA2") (pinfunction "OUT-A_OUTA2") (pintype "bidirectional"))
      (node (ref "M5") (pin "OUTA3") (pinfunction "OUT-A_OUTA3") (pintype "bidirectional"))
    )
    (net (code "58") (name "M5-") (class "Default")
      (node (ref "D-SUB50") (pin "46") (pinfunction "46_46") (pintype "passive"))
      (node (ref "M5") (pin "OUTB") (pinfunction "OUT-B_OUTB") (pintype "bidirectional"))
      (node (ref "M5") (pin "OUTB1") (pinfunction "OUT-B_OUTB1") (pintype "bidirectional"))
      (node (ref "M5") (pin "OUTB3") (pinfunction "OUT-B_OUTB3") (pintype "bidirectional"))
    )
    (net (code "59") (name "M5-FUSE") (class "Default")
      (node (ref "F5") (pin "1") (pinfunction "1_1") (pintype "passive"))
      (node (ref "M5") (pin "VIN0") (pinfunction "+12V_VIN0") (pintype "bidirectional"))
      (node (ref "M5") (pin "VIN1") (pinfunction "+12V_VIN1") (pintype "bidirectional"))
      (node (ref "M5") (pin "VIN2") (pinfunction "+12V_VIN2") (pintype "bidirectional"))
    )
    (net (code "60") (name "M6+") (class "Default")
      (node (ref "D-SUB50") (pin "12") (pinfunction "12_12") (pintype "passive"))
      (node (ref "M6") (pin "OUTA") (pinfunction "OUT-A_OUTA") (pintype "bidirectional"))
      (node (ref "M6") (pin "OUTA2") (pinfunction "OUT-A_OUTA2") (pintype "bidirectional"))
      (node (ref "M6") (pin "OUTA3") (pinfunction "OUT-A_OUTA3") (pintype "bidirectional"))
    )
    (net (code "61") (name "M6-") (class "Default")
      (node (ref "D-SUB50") (pin "45") (pinfunction "45_45") (pintype "passive"))
      (node (ref "M6") (pin "OUTB") (pinfunction "OUT-B_OUTB") (pintype "bidirectional"))
      (node (ref "M6") (pin "OUTB1") (pinfunction "OUT-B_OUTB1") (pintype "bidirectional"))
      (node (ref "M6") (pin "OUTB3") (pinfunction "OUT-B_OUTB3") (pintype "bidirectional"))
    )
    (net (code "62") (name "M6-FUSE") (class "Default")
      (node (ref "F6") (pin "1") (pinfunction "1_1") (pintype "passive"))
      (node (ref "M6") (pin "VIN0") (pinfunction "+12V_VIN0") (pintype "bidirectional"))
      (node (ref "M6") (pin "VIN1") (pinfunction "+12V_VIN1") (pintype "bidirectional"))
      (node (ref "M6") (pin "VIN2") (pinfunction "+12V_VIN2") (pintype "bidirectional"))
    )
    (net (code "63") (name "MOT-EN") (class "Default")
      (node (ref "ARDUINO_MEGA_1") (pin "D38") (pinfunction "D38(PD7/T0)_D38") (pintype "bidirectional"))
      (node (ref "M1") (pin "ENA") (pinfunction "ENA_ENA") (pintype "bidirectional"))
      (node (ref "M1") (pin "ENB") (pinfunction "ENB_ENB") (pintype "bidirectional"))
      (node (ref "M2") (pin "ENA") (pinfunction "ENA_ENA") (pintype "bidirectional"))
      (node (ref "M2") (pin "ENB") (pinfunction "ENB_ENB") (pintype "bidirectional"))
      (node (ref "M3") (pin "ENA") (pinfunction "ENA_ENA") (pintype "bidirectional"))
      (node (ref "M3") (pin "ENB") (pinfunction "ENB_ENB") (pintype "bidirectional"))
      (node (ref "M4") (pin "ENA") (pinfunction "ENA_ENA") (pintype "bidirectional"))
      (node (ref "M4") (pin "ENB") (pinfunction "ENB_ENB") (pintype "bidirectional"))
      (node (ref "M5") (pin "ENA") (pinfunction "ENA_ENA") (pintype "bidirectional"))
      (node (ref "M5") (pin "ENB") (pinfunction "ENB_ENB") (pintype "bidirectional"))
      (node (ref "M6") (pin "ENA") (pinfunction "ENA_ENA") (pintype "bidirectional"))
      (node (ref "M6") (pin "ENB") (pinfunction "ENB_ENB") (pintype "bidirectional"))
    )
    (net (code "64") (name "MS1") (class "Default")
      (node (ref "ARDUINO_MEGA_1") (pin "D37") (pinfunction "D37(PC0/A8)_D37") (pintype "bidirectional"))
      (node (ref "D-SUB50") (pin "23") (pinfunction "23_23") (pintype "passive"))
    )
    (net (code "65") (name "MS2") (class "Default")
      (node (ref "ARDUINO_MEGA_1") (pin "D36") (pinfunction "D36(PC1/A9)_D36") (pintype "bidirectional"))
      (node (ref "D-SUB50") (pin "7") (pinfunction "7_7") (pintype "passive"))
    )
    (net (code "66") (name "MS3") (class "Default")
      (node (ref "ARDUINO_MEGA_1") (pin "D35") (pinfunction "D35(PC2/A10)_D35") (pintype "bidirectional"))
      (node (ref "D-SUB50") (pin "24") (pinfunction "24_24") (pintype "passive"))
    )
    (net (code "67") (name "MS4") (class "Default")
      (node (ref "ARDUINO_MEGA_1") (pin "D34") (pinfunction "D34(PC3/A11)_D34") (pintype "bidirectional"))
      (node (ref "D-SUB50") (pin "8") (pinfunction "8_8") (pintype "passive"))
    )
    (net (code "68") (name "MS5") (class "Default")
      (node (ref "ARDUINO_MEGA_1") (pin "D33") (pinfunction "D33(PC4/A12)_D33") (pintype "bidirectional"))
      (node (ref "D-SUB50") (pin "6") (pinfunction "6_6") (pintype "passive"))
    )
    (net (code "69") (name "MS6") (class "Default")
      (node (ref "ARDUINO_MEGA_1") (pin "D32") (pinfunction "D32(PC5/A13)_D32") (pintype "bidirectional"))
      (node (ref "D-SUB50") (pin "22") (pinfunction "22_22") (pintype "passive"))
    )
    (net (code "70") (name "Net-(ARDUINO_MEGA_1-~{RESET})") (class "Default")
      (node (ref "ARDUINO_MEGA_1") (pin "RST") (pinfunction "~{RESET}_RST") (pintype "bidirectional"))
      (node (ref "RESET-LOGIC") (pin "1") (pinfunction "1_1") (pintype "passive"))
    )
    (net (code "71") (name "Net-(MOT-SWA-KL)") (class "Default")
      (node (ref "D1") (pin "A") (pinfunction "A_A") (pintype "passive"))
      (node (ref "MOT-SW") (pin "1") (pinfunction "KL_1") (pintype "passive"))
    )
    (net (code "72") (name "Net-(P-ON-PadA)") (class "Default")
      (node (ref "P-ON") (pin "A") (pinfunction "A_A") (pintype "passive"))
      (node (ref "RL") (pin "1") (pinfunction "1_1") (pintype "passive"))
    )
    (net (code "73") (name "Net-(R-REF-S)") (class "Default")
      (node (ref "AREF-JP") (pin "2") (pinfunction "2_2") (pintype "passive"))
      (node (ref "R-REF") (pin "2") (pinfunction "S_2") (pintype "passive"))
      (node (ref "V-REF-PAD") (pin "TP-1") (pinfunction "TP_TP-1") (pintype "input"))
    )
    (net (code "74") (name "Net-(VTEST-A-TP)") (class "Default")
      (node (ref "SJ2") (pin "1") (pinfunction "1_1") (pintype "passive"))
      (node (ref "SP-DW") (pin "OUT+") (pinfunction "OUT+_OUT+") (pintype "bidirectional"))
      (node (ref "SP-DW") (pin "OUT+1") (pinfunction "OUT+_OUT+1") (pintype "bidirectional"))
      (node (ref "SP-DW") (pin "OUT+2") (pinfunction "OUT+_OUT+2") (pintype "bidirectional"))
      (node (ref "VTEST-") (pin "TP-1") (pinfunction "TP_TP-1") (pintype "input"))
    )
    (net (code "75") (name "PWM1") (class "Default")
      (node (ref "ARDUINO_MEGA_1") (pin "D5") (pinfunction "(PWM)D05(PE3/AIN1/OC3A)_D5") (pintype "bidirectional"))
      (node (ref "M1") (pin "PWM") (pinfunction "PWM_PWM") (pintype "bidirectional"))
    )
    (net (code "76") (name "PWM2") (class "Default")
      (node (ref "ARDUINO_MEGA_1") (pin "D2") (pinfunction "(PWM)D02(PE4/INT4/OC3B)_D2") (pintype "bidirectional"))
      (node (ref "M2") (pin "PWM") (pinfunction "PWM_PWM") (pintype "bidirectional"))
    )
    (net (code "77") (name "PWM3") (class "Default")
      (node (ref "ARDUINO_MEGA_1") (pin "D3") (pinfunction "(PWM)D03(PE5/INT5/OC3C)_D3") (pintype "bidirectional"))
      (node (ref "M3") (pin "PWM") (pinfunction "PWM_PWM") (pintype "bidirectional"))
    )
    (net (code "78") (name "PWM4") (class "Default")
      (node (ref "ARDUINO_MEGA_1") (pin "D6") (pinfunction "(PWM)D06(PH3/OC4A)_D6") (pintype "bidirectional"))
      (node (ref "M4") (pin "PWM") (pinfunction "PWM_PWM") (pintype "bidirectional"))
    )
    (net (code "79") (name "PWM5") (class "Default")
      (node (ref "ARDUINO_MEGA_1") (pin "D7") (pinfunction "(PWM)D07(PH4/OC4B)_D7") (pintype "bidirectional"))
      (node (ref "M5") (pin "PWM") (pinfunction "PWM_PWM") (pintype "bidirectional"))
    )
    (net (code "80") (name "PWM6") (class "Default")
      (node (ref "ARDUINO_MEGA_1") (pin "D8") (pinfunction "(PWM)D08(PH5/OC4C)_D8") (pintype "bidirectional"))
      (node (ref "M6") (pin "PWM") (pinfunction "PWM_PWM") (pintype "bidirectional"))
    )
    (net (code "81") (name "RP-ARX{slash}PTX") (class "Default")
      (node (ref "RASPBERRY-PY") (pin "8") (pinfunction "TXD_8") (pintype "bidirectional"))
      (node (ref "SV1") (pin "5") (pinfunction "5_5") (pintype "passive"))
      (node (ref "U1") (pin "6") (pinfunction "A5_6") (pintype "bidirectional"))
    )
    (net (code "82") (name "RP-ATX{slash}PRX") (class "Default")
      (node (ref "RASPBERRY-PY") (pin "10") (pinfunction "RXD_10") (pintype "bidirectional"))
      (node (ref "SV1") (pin "6") (pinfunction "6_6") (pintype "passive"))
      (node (ref "U1") (pin "7") (pinfunction "A6_7") (pintype "bidirectional"))
    )
    (net (code "83") (name "RP-MISO") (class "Default")
      (node (ref "RASPBERRY-PY") (pin "21") (pinfunction "SPI_MISO_21") (pintype "bidirectional"))
      (node (ref "SV1") (pin "2") (pinfunction "2_2") (pintype "passive"))
      (node (ref "U1") (pin "3") (pinfunction "A2_3") (pintype "bidirectional"))
    )
    (net (code "84") (name "RP-MOSI") (class "Default")
      (node (ref "RASPBERRY-PY") (pin "19") (pinfunction "SPI_MOSI_19") (pintype "bidirectional"))
      (node (ref "SV1") (pin "1") (pinfunction "1_1") (pintype "passive"))
      (node (ref "U1") (pin "1") (pinfunction "A1_1") (pintype "bidirectional"))
    )
    (net (code "85") (name "RP-SCK") (class "Default")
      (node (ref "RASPBERRY-PY") (pin "23") (pinfunction "SPI_SCLK_23") (pintype "bidirectional"))
      (node (ref "SV1") (pin "3") (pinfunction "3_3") (pintype "passive"))
      (node (ref "U1") (pin "4") (pinfunction "A3_4") (pintype "bidirectional"))
    )
    (net (code "86") (name "RP-SCL") (class "Default")
      (node (ref "RASPBERRY-PY") (pin "5") (pinfunction "SCL_5") (pintype "bidirectional"))
      (node (ref "SV1") (pin "8") (pinfunction "8_8") (pintype "passive"))
      (node (ref "U1") (pin "9") (pinfunction "A8_9") (pintype "bidirectional"))
    )
    (net (code "87") (name "RP-SDA") (class "Default")
      (node (ref "RASPBERRY-PY") (pin "3") (pinfunction "SDA_3") (pintype "bidirectional"))
      (node (ref "SV1") (pin "7") (pinfunction "7_7") (pintype "passive"))
      (node (ref "U1") (pin "8") (pinfunction "A7_8") (pintype "bidirectional"))
    )
    (net (code "88") (name "RP-SS") (class "Default")
      (node (ref "RASPBERRY-PY") (pin "24") (pinfunction "SPI_CE0_24") (pintype "bidirectional"))
      (node (ref "SV1") (pin "4") (pinfunction "4_4") (pintype "passive"))
      (node (ref "U1") (pin "5") (pinfunction "A4_5") (pintype "bidirectional"))
    )
    (net (code "89") (name "V+") (class "Default")
      (node (ref "MOT-SW") (pin "2") (pinfunction "KL_2") (pintype "passive"))
      (node (ref "PWR") (pin "2") (pinfunction "KL_2") (pintype "passive"))
      (node (ref "SP-DW") (pin "IN+") (pinfunction "IN+_IN+") (pintype "bidirectional"))
      (node (ref "SP-DW") (pin "IN+1") (pinfunction "IN+_IN+1") (pintype "bidirectional"))
      (node (ref "SP-DW") (pin "IN+2") (pinfunction "IN+_IN+2") (pintype "bidirectional"))
    )
    (net (code "90") (name "V-OFF") (class "Default")
      (node (ref "ARDUINO_MEGA_1") (pin "A1") (pinfunction "A01(PF1/ADC1)_A1") (pintype "bidirectional"))
      (node (ref "C3") (pin "1") (pinfunction "1_1") (pintype "passive"))
      (node (ref "R-OFF") (pin "2") (pinfunction "S_2") (pintype "passive"))
      (node (ref "V-OFF-PAD") (pin "TP-1") (pinfunction "TP_TP-1") (pintype "input"))
    )
    (net (code "91") (name "V-REF") (class "Default")
      (node (ref "ARDUINO_MEGA_1") (pin "AREF") (pinfunction "AREF_AREF") (pintype "bidirectional"))
      (node (ref "AREF-JP") (pin "1") (pinfunction "1_1") (pintype "passive"))
      (node (ref "C2") (pin "1") (pinfunction "1_1") (pintype "passive"))
    )
    (net (code "92") (name "VDD") (class "Default")
      (node (ref "C1") (pin "+") (pinfunction "+_+") (pintype "passive"))
      (node (ref "D1") (pin "C") (pinfunction "C_C") (pintype "passive"))
      (node (ref "F1") (pin "2") (pinfunction "2_2") (pintype "passive"))
      (node (ref "F2") (pin "2") (pinfunction "2_2") (pintype "passive"))
      (node (ref "F3") (pin "2") (pinfunction "2_2") (pintype "passive"))
      (node (ref "F4") (pin "2") (pinfunction "2_2") (pintype "passive"))
      (node (ref "F5") (pin "2") (pinfunction "2_2") (pintype "passive"))
      (node (ref "F6") (pin "2") (pinfunction "2_2") (pintype "passive"))
      (node (ref "FAN-PWR") (pin "1") (pinfunction "KL_1") (pintype "passive"))
    )
    (net (code "93") (name "VLED1") (class "Default")
      (node (ref "D-SUB50") (pin "11") (pinfunction "11_11") (pintype "passive"))
      (node (ref "R1") (pin "2") (pinfunction "2_2") (pintype "passive"))
    )
    (net (code "94") (name "VLED2") (class "Default")
      (node (ref "D-SUB50") (pin "27") (pinfunction "27_27") (pintype "passive"))
      (node (ref "R2") (pin "2") (pinfunction "2_2") (pintype "passive"))
    )
    (net (code "95") (name "VLED3") (class "Default")
      (node (ref "D-SUB50") (pin "10") (pinfunction "10_10") (pintype "passive"))
      (node (ref "R3") (pin "2") (pinfunction "2_2") (pintype "passive"))
    )
    (net (code "96") (name "VLED4") (class "Default")
      (node (ref "D-SUB50") (pin "26") (pinfunction "26_26") (pintype "passive"))
      (node (ref "R4") (pin "2") (pinfunction "2_2") (pintype "passive"))
    )
    (net (code "97") (name "VLED5") (class "Default")
      (node (ref "D-SUB50") (pin "9") (pinfunction "9_9") (pintype "passive"))
      (node (ref "R5") (pin "2") (pinfunction "2_2") (pintype "passive"))
    )
    (net (code "98") (name "VLED6") (class "Default")
      (node (ref "D-SUB50") (pin "25") (pinfunction "25_25") (pintype "passive"))
      (node (ref "R6") (pin "2") (pinfunction "2_2") (pintype "passive"))
    )
    (net (code "99") (name "unconnected-(ARDUINO_MEGA_1-(PWM)D04(PG5{slash}OC0B)-PadD4)") (class "Default")
      (node (ref "ARDUINO_MEGA_1") (pin "D4") (pinfunction "(PWM)D04(PG5/OC0B)_D4") (pintype "bidirectional"))
    )
    (net (code "100") (name "unconnected-(ARDUINO_MEGA_1-(PWM)D09(PH6{slash}OC2B)-PadD9)") (class "Default")
      (node (ref "ARDUINO_MEGA_1") (pin "D9") (pinfunction "(PWM)D09(PH6/OC2B)_D9") (pintype "bidirectional"))
    )
    (net (code "101") (name "unconnected-(ARDUINO_MEGA_1-(PWM)D44(PL5{slash}OC5C)-PadD44)") (class "Default")
      (node (ref "ARDUINO_MEGA_1") (pin "D44") (pinfunction "(PWM)D44(PL5/OC5C)_D44") (pintype "bidirectional"))
    )
    (net (code "102") (name "unconnected-(ARDUINO_MEGA_1-(PWM)D45(PL4{slash}OC5B)-PadD45)") (class "Default")
      (node (ref "ARDUINO_MEGA_1") (pin "D45") (pinfunction "(PWM)D45(PL4/OC5B)_D45") (pintype "bidirectional"))
    )
    (net (code "103") (name "unconnected-(ARDUINO_MEGA_1-(RX)D00(PE0{slash}TXD0{slash}PCINT8)-PadD0)") (class "Default")
      (node (ref "ARDUINO_MEGA_1") (pin "D0") (pinfunction "(RX)D00(PE0/TXD0/PCINT8)_D0") (pintype "bidirectional"))
    )
    (net (code "104") (name "unconnected-(ARDUINO_MEGA_1-(RX2)D17(PH0{slash}RXD2)-PadD17)") (class "Default")
      (node (ref "ARDUINO_MEGA_1") (pin "D17") (pinfunction "(RX2)D17(PH0/RXD2)_D17") (pintype "bidirectional"))
    )
    (net (code "105") (name "unconnected-(ARDUINO_MEGA_1-(RX3)D15(PJ0{slash}PCINT9{slash}RXD3)-PadD15)") (class "Default")
      (node (ref "ARDUINO_MEGA_1") (pin "D15") (pinfunction "(RX3)D15(PJ0/PCINT9/RXD3)_D15") (pintype "bidirectional"))
    )
    (net (code "106") (name "unconnected-(ARDUINO_MEGA_1-(TX)D01(PE1{slash}RXD0{slash}PCINT3)-PadD1)") (class "Default")
      (node (ref "ARDUINO_MEGA_1") (pin "D1") (pinfunction "(TX)D01(PE1/RXD0/PCINT3)_D1") (pintype "bidirectional"))
    )
    (net (code "107") (name "unconnected-(ARDUINO_MEGA_1-(TX2)D16(PH1{slash}TXD2)-PadD16)") (class "Default")
      (node (ref "ARDUINO_MEGA_1") (pin "D16") (pinfunction "(TX2)D16(PH1/TXD2)_D16") (pintype "bidirectional"))
    )
    (net (code "108") (name "unconnected-(ARDUINO_MEGA_1-(TX3)D14(PJ1{slash}PCINT10{slash}TXD3)-PadD14)") (class "Default")
      (node (ref "ARDUINO_MEGA_1") (pin "D14") (pinfunction "(TX3)D14(PJ1/PCINT10/TXD3)_D14") (pintype "bidirectional"))
    )
    (net (code "109") (name "unconnected-(ARDUINO_MEGA_1-+VIN-PadVIN)") (class "Default")
      (node (ref "ARDUINO_MEGA_1") (pin "VIN") (pinfunction "+VIN_VIN") (pintype "bidirectional"))
    )
    (net (code "110") (name "unconnected-(ARDUINO_MEGA_1-A07(PF7{slash}ADC7{slash}TDI)-PadA7)") (class "Default")
      (node (ref "ARDUINO_MEGA_1") (pin "A7") (pinfunction "A07(PF7/ADC7/TDI)_A7") (pintype "bidirectional"))
    )
    (net (code "111") (name "unconnected-(ARDUINO_MEGA_1-D30(PC7{slash}A15)-PadD30)") (class "Default")
      (node (ref "ARDUINO_MEGA_1") (pin "D30") (pinfunction "D30(PC7/A15)_D30") (pintype "bidirectional"))
    )
    (net (code "112") (name "unconnected-(ARDUINO_MEGA_1-D31(PC6{slash}A14)-PadD31)") (class "Default")
      (node (ref "ARDUINO_MEGA_1") (pin "D31") (pinfunction "D31(PC6/A14)_D31") (pintype "bidirectional"))
    )
    (net (code "113") (name "unconnected-(ARDUINO_MEGA_1-D39(PG2{slash}ALE)-PadD39)") (class "Default")
      (node (ref "ARDUINO_MEGA_1") (pin "D39") (pinfunction "D39(PG2/ALE)_D39") (pintype "bidirectional"))
    )
    (net (code "114") (name "unconnected-(ARDUINO_MEGA_1-D40(PG1{slash}RD)-PadD40)") (class "Default")
      (node (ref "ARDUINO_MEGA_1") (pin "D40") (pinfunction "D40(PG1/RD)_D40") (pintype "bidirectional"))
    )
    (net (code "115") (name "unconnected-(ARDUINO_MEGA_1-D41(PG0{slash}WR)-PadD41)") (class "Default")
      (node (ref "ARDUINO_MEGA_1") (pin "D41") (pinfunction "D41(PG0/WR)_D41") (pintype "bidirectional"))
    )
    (net (code "116") (name "unconnected-(ARDUINO_MEGA_1-D42(PL7)-PadD42)") (class "Default")
      (node (ref "ARDUINO_MEGA_1") (pin "D42") (pinfunction "D42(PL7)_D42") (pintype "bidirectional"))
    )
    (net (code "117") (name "unconnected-(ARDUINO_MEGA_1-D43(PL6)-PadD43)") (class "Default")
      (node (ref "ARDUINO_MEGA_1") (pin "D43") (pinfunction "D43(PL6)_D43") (pintype "bidirectional"))
    )
    (net (code "118") (name "unconnected-(ARDUINO_MEGA_1-PadIOREF)") (class "Default")
      (node (ref "ARDUINO_MEGA_1") (pin "IOREF") (pinfunction "IOREF_IOREF") (pintype "bidirectional"))
    )
    (net (code "119") (name "unconnected-(D-SUB50-Pad37)") (class "Default")
      (node (ref "D-SUB50") (pin "37") (pinfunction "37_37") (pintype "passive"))
    )
    (net (code "120") (name "unconnected-(D-SUB50-Pad38)") (class "Default")
      (node (ref "D-SUB50") (pin "38") (pinfunction "38_38") (pintype "passive"))
    )
    (net (code "121") (name "unconnected-(D-SUB50-Pad39)") (class "Default")
      (node (ref "D-SUB50") (pin "39") (pinfunction "39_39") (pintype "passive"))
    )
    (net (code "122") (name "unconnected-(D-SUB50-Pad40)") (class "Default")
      (node (ref "D-SUB50") (pin "40") (pinfunction "40_40") (pintype "passive"))
    )
    (net (code "123") (name "unconnected-(D-SUB50-Pad41)") (class "Default")
      (node (ref "D-SUB50") (pin "41") (pinfunction "41_41") (pintype "passive"))
    )
    (net (code "124") (name "unconnected-(D-SUB50-Pad42)") (class "Default")
      (node (ref "D-SUB50") (pin "42") (pinfunction "42_42") (pintype "passive"))
    )
    (net (code "125") (name "unconnected-(D-SUB50-Pad43)") (class "Default")
      (node (ref "D-SUB50") (pin "43") (pinfunction "43_43") (pintype "passive"))
    )
    (net (code "126") (name "unconnected-(D-SUB50-Pad44)") (class "Default")
      (node (ref "D-SUB50") (pin "44") (pinfunction "44_44") (pintype "passive"))
    )
    (net (code "127") (name "unconnected-(D-SUB50-PadG1)") (class "Default")
      (node (ref "D-SUB50") (pin "G1") (pinfunction "G1_G1") (pintype "passive"))
    )
    (net (code "128") (name "unconnected-(D-SUB50-PadG2)") (class "Default")
      (node (ref "D-SUB50") (pin "G2") (pinfunction "G2_G2") (pintype "passive"))
    )
    (net (code "129") (name "unconnected-(RASPBERRY-PY-GPIO04-Pad7)") (class "Default")
      (node (ref "RASPBERRY-PY") (pin "7") (pinfunction "GPIO04_7") (pintype "bidirectional"))
    )
    (net (code "130") (name "unconnected-(RASPBERRY-PY-GPIO05-Pad29)") (class "Default")
      (node (ref "RASPBERRY-PY") (pin "29") (pinfunction "GPIO05_29") (pintype "no_connect"))
    )
    (net (code "131") (name "unconnected-(RASPBERRY-PY-GPIO06-Pad31)") (class "Default")
      (node (ref "RASPBERRY-PY") (pin "31") (pinfunction "GPIO06_31") (pintype "no_connect"))
    )
    (net (code "132") (name "unconnected-(RASPBERRY-PY-GPIO12-Pad32)") (class "Default")
      (node (ref "RASPBERRY-PY") (pin "32") (pinfunction "GPIO12_32") (pintype "no_connect"))
    )
    (net (code "133") (name "unconnected-(RASPBERRY-PY-GPIO13-Pad33)") (class "Default")
      (node (ref "RASPBERRY-PY") (pin "33") (pinfunction "GPIO13_33") (pintype "no_connect"))
    )
    (net (code "134") (name "unconnected-(RASPBERRY-PY-GPIO16-Pad36)") (class "Default")
      (node (ref "RASPBERRY-PY") (pin "36") (pinfunction "GPIO16_36") (pintype "no_connect"))
    )
    (net (code "135") (name "unconnected-(RASPBERRY-PY-GPIO18-Pad12)") (class "Default")
      (node (ref "RASPBERRY-PY") (pin "12") (pinfunction "GPIO18_12") (pintype "bidirectional"))
    )
    (net (code "136") (name "unconnected-(RASPBERRY-PY-GPIO19-Pad35)") (class "Default")
      (node (ref "RASPBERRY-PY") (pin "35") (pinfunction "GPIO19_35") (pintype "no_connect"))
    )
    (net (code "137") (name "unconnected-(RASPBERRY-PY-GPIO20-Pad38)") (class "Default")
      (node (ref "RASPBERRY-PY") (pin "38") (pinfunction "GPIO20_38") (pintype "no_connect"))
    )
    (net (code "138") (name "unconnected-(RASPBERRY-PY-GPIO21-Pad40)") (class "Default")
      (node (ref "RASPBERRY-PY") (pin "40") (pinfunction "GPIO21_40") (pintype "no_connect"))
    )
    (net (code "139") (name "unconnected-(RASPBERRY-PY-GPIO22-Pad15)") (class "Default")
      (node (ref "RASPBERRY-PY") (pin "15") (pinfunction "GPIO22_15") (pintype "bidirectional"))
    )
    (net (code "140") (name "unconnected-(RASPBERRY-PY-GPIO23-Pad16)") (class "Default")
      (node (ref "RASPBERRY-PY") (pin "16") (pinfunction "GPIO23_16") (pintype "bidirectional"))
    )
    (net (code "141") (name "unconnected-(RASPBERRY-PY-GPIO24-Pad18)") (class "Default")
      (node (ref "RASPBERRY-PY") (pin "18") (pinfunction "GPIO24_18") (pintype "bidirectional"))
    )
    (net (code "142") (name "unconnected-(RASPBERRY-PY-GPIO25-Pad22)") (class "Default")
      (node (ref "RASPBERRY-PY") (pin "22") (pinfunction "GPIO25_22") (pintype "bidirectional"))
    )
    (net (code "143") (name "unconnected-(RASPBERRY-PY-GPIO26-Pad37)") (class "Default")
      (node (ref "RASPBERRY-PY") (pin "37") (pinfunction "GPIO26_37") (pintype "no_connect"))
    )
    (net (code "144") (name "unconnected-(RASPBERRY-PY-GPIO27-Pad13)") (class "Default")
      (node (ref "RASPBERRY-PY") (pin "13") (pinfunction "GPIO27_13") (pintype "bidirectional"))
    )
    (net (code "145") (name "unconnected-(RASPBERRY-PY-ID_SC-Pad28)") (class "Default")
      (node (ref "RASPBERRY-PY") (pin "28") (pinfunction "ID_SC_28") (pintype "no_connect"))
    )
    (net (code "146") (name "unconnected-(RASPBERRY-PY-ID_SD-Pad27)") (class "Default")
      (node (ref "RASPBERRY-PY") (pin "27") (pinfunction "ID_SD_27") (pintype "no_connect"))
    )
    (net (code "147") (name "unconnected-(RASPBERRY-PY-N.C.0-Pad4)") (class "Default")
      (node (ref "RASPBERRY-PY") (pin "4") (pinfunction "N.C.0_4") (pintype "no_connect"))
    )
    (net (code "148") (name "unconnected-(RASPBERRY-PY-N.C.1-Pad9)") (class "Default")
      (node (ref "RASPBERRY-PY") (pin "9") (pinfunction "N.C.1_9") (pintype "no_connect"))
    )
    (net (code "149") (name "unconnected-(RASPBERRY-PY-N.C.2-Pad14)") (class "Default")
      (node (ref "RASPBERRY-PY") (pin "14") (pinfunction "N.C.2_14") (pintype "no_connect"))
    )
    (net (code "150") (name "unconnected-(RASPBERRY-PY-N.C.3-Pad17)") (class "Default")
      (node (ref "RASPBERRY-PY") (pin "17") (pinfunction "N.C.3_17") (pintype "no_connect"))
    )
    (net (code "151") (name "unconnected-(RASPBERRY-PY-N.C.4-Pad20)") (class "Default")
      (node (ref "RASPBERRY-PY") (pin "20") (pinfunction "N.C.4_20") (pintype "no_connect"))
    )
    (net (code "152") (name "unconnected-(RASPBERRY-PY-N.C.5-Pad25)") (class "Default")
      (node (ref "RASPBERRY-PY") (pin "25") (pinfunction "N.C.5_25") (pintype "no_connect"))
    )
    (net (code "153") (name "unconnected-(RASPBERRY-PY-N.C.6-Pad30)") (class "Default")
      (node (ref "RASPBERRY-PY") (pin "30") (pinfunction "N.C.6_30") (pintype "no_connect"))
    )
    (net (code "154") (name "unconnected-(RASPBERRY-PY-N.C.7-Pad34)") (class "Default")
      (node (ref "RASPBERRY-PY") (pin "34") (pinfunction "N.C.7_34") (pintype "no_connect"))
    )
    (net (code "155") (name "unconnected-(RASPBERRY-PY-N.C.8-Pad39)") (class "Default")
      (node (ref "RASPBERRY-PY") (pin "39") (pinfunction "N.C.8_39") (pintype "no_connect"))
    )
    (net (code "156") (name "unconnected-(RASPBERRY-PY-SPI_CE1-Pad26)") (class "Default")
      (node (ref "RASPBERRY-PY") (pin "26") (pinfunction "SPI_CE1_26") (pintype "bidirectional"))
    )
  )
)
